# projeson1.net
KiCad netlist of a schematic drawn in EAGLE
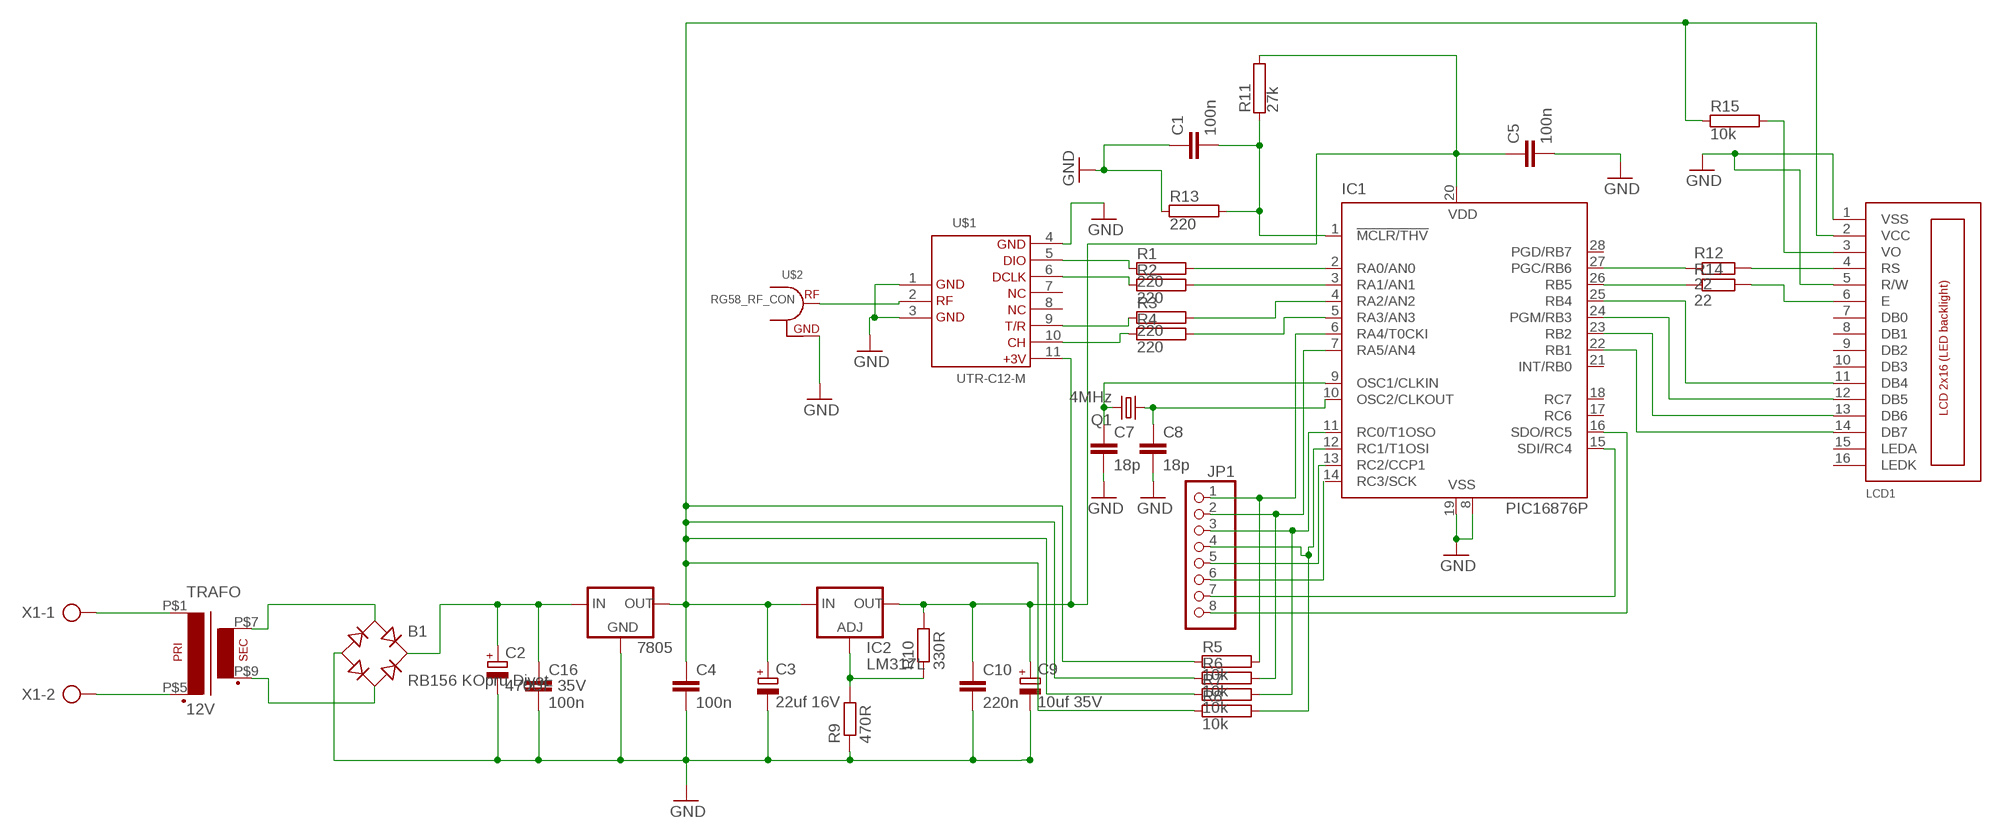
[diagram p0: schematic, sheet 1]

(export (version "E")
  (design (tool "Eeschema 10.0.6"))
  (components
    (comp (ref "7805")
      (value "78XXS")
      (footprint "eagle-import:78XXS")
      (libsource (lib "eagle-import") (part "78XXS"))
    )
    (comp (ref "B1")
      (value "RB156 KOpru Diyot")
      (footprint "eagle-import:RB1A")
      (libsource (lib "eagle-import") (part "RB1A"))
    )
    (comp (ref "C1")
      (value "100n")
      (footprint "eagle-import:C025-030X050")
      (libsource (lib "eagle-import") (part "C-EU025-030X050"))
    )
    (comp (ref "C2")
      (value "470UF 35V")
      (footprint "eagle-import:E3,5-10")
      (libsource (lib "eagle-import") (part "CPOL-EUE3.5-10"))
    )
    (comp (ref "C3")
      (value "22uf 16V")
      (footprint "eagle-import:E2,5-7")
      (libsource (lib "eagle-import") (part "CPOL-EUE2.5-7"))
    )
    (comp (ref "C4")
      (value "100n")
      (footprint "eagle-import:C050-025X075")
      (libsource (lib "eagle-import") (part "C-EU050-025X075"))
    )
    (comp (ref "C5")
      (value "100n")
      (footprint "eagle-import:C025-025X050")
      (libsource (lib "eagle-import") (part "C-EU025-025X050"))
    )
    (comp (ref "C7")
      (value "18p")
      (footprint "eagle-import:C025-025X050")
      (libsource (lib "eagle-import") (part "C-EU025-025X050"))
    )
    (comp (ref "C8")
      (value "18p")
      (footprint "eagle-import:C025-025X050")
      (libsource (lib "eagle-import") (part "C-EU025-025X050"))
    )
    (comp (ref "C9")
      (value "10uf 35V")
      (footprint "eagle-import:E2,5-7")
      (libsource (lib "eagle-import") (part "CPOL-EUE2.5-7"))
    )
    (comp (ref "C10")
      (value "220n")
      (footprint "eagle-import:C050-025X075")
      (libsource (lib "eagle-import") (part "C-EU050-025X075"))
    )
    (comp (ref "C16")
      (value "100n")
      (footprint "eagle-import:C050-025X075")
      (libsource (lib "eagle-import") (part "C-EU050-025X075"))
    )
    (comp (ref "IC1")
      (value "PIC16876P")
      (footprint "eagle-import:DIL28-3")
      (libsource (lib "eagle-import") (part "PIC16876P"))
    )
    (comp (ref "IC2")
      (value "LM317L")
      (footprint "eagle-import:317L")
      (libsource (lib "eagle-import") (part "LM317L"))
    )
    (comp (ref "JP1")
      (value "PINHD-1X8")
      (footprint "eagle-import:1X08")
      (libsource (lib "eagle-import") (part "PINHD-1X8"))
    )
    (comp (ref "LCD1")
      (value "LCD_2X16_SIL")
      (footprint "eagle-import:HY-1602F")
      (libsource (lib "eagle-import") (part "LCD_2X16_SIL"))
    )
    (comp (ref "Q1")
      (value "4MHz")
      (footprint "eagle-import:HC49_S")
      (libsource (lib "eagle-import") (part "CRYTALHC49S"))
    )
    (comp (ref "R1")
      (value "220")
      (footprint "eagle-import:AC04")
      (libsource (lib "eagle-import") (part "RAC04"))
    )
    (comp (ref "R2")
      (value "220")
      (footprint "eagle-import:AC04")
      (libsource (lib "eagle-import") (part "RAC04"))
    )
    (comp (ref "R3")
      (value "220")
      (footprint "eagle-import:AC04")
      (libsource (lib "eagle-import") (part "RAC04"))
    )
    (comp (ref "R4")
      (value "220")
      (footprint "eagle-import:AC04")
      (libsource (lib "eagle-import") (part "RAC04"))
    )
    (comp (ref "R5")
      (value "10k")
      (footprint "eagle-import:AC04")
      (libsource (lib "eagle-import") (part "RAC04"))
    )
    (comp (ref "R6")
      (value "10k")
      (footprint "eagle-import:AC04")
      (libsource (lib "eagle-import") (part "RAC04"))
    )
    (comp (ref "R7")
      (value "10k")
      (footprint "eagle-import:AC04")
      (libsource (lib "eagle-import") (part "RAC04"))
    )
    (comp (ref "R8")
      (value "10k")
      (footprint "eagle-import:AC04")
      (libsource (lib "eagle-import") (part "RAC04"))
    )
    (comp (ref "R9")
      (value "470R")
      (footprint "eagle-import:0207_10")
      (libsource (lib "eagle-import") (part "R-EU_0207/10"))
    )
    (comp (ref "R10")
      (value "330R")
      (footprint "eagle-import:0207_10")
      (libsource (lib "eagle-import") (part "R-EU_0207/10"))
    )
    (comp (ref "R11")
      (value "27k")
      (footprint "eagle-import:AC04")
      (libsource (lib "eagle-import") (part "RAC04"))
    )
    (comp (ref "R12")
      (value "22")
      (footprint "eagle-import:0204_5")
      (libsource (lib "eagle-import") (part "R-EU_0204/5"))
    )
    (comp (ref "R13")
      (value "220")
      (footprint "eagle-import:AC04")
      (libsource (lib "eagle-import") (part "RAC04"))
    )
    (comp (ref "R14")
      (value "22")
      (footprint "eagle-import:0204_5")
      (libsource (lib "eagle-import") (part "R-EU_0204/5"))
    )
    (comp (ref "R15")
      (value "10k")
      (footprint "eagle-import:AC04")
      (libsource (lib "eagle-import") (part "RAC04"))
    )
    (comp (ref "TRAFO")
      (value "12V")
      (footprint "eagle-import:E3031TRF")
      (libsource (lib "eagle-import") (part "TRAFO"))
    )
    (comp (ref "U$1")
      (value "UTR-C12-M")
      (footprint "eagle-import:UTR-C12-M")
      (libsource (lib "eagle-import") (part "UTR-C12-M"))
    )
    (comp (ref "U$2")
      (value "RG58_RF_CON")
      (footprint "eagle-import:RG58_RF_CON")
      (libsource (lib "eagle-import") (part "RG58_RF_CON"))
    )
    (comp (ref "X1")
      (value "AK300/3")
      (footprint "eagle-import:AK300_3")
      (libsource (lib "eagle-import") (part "AK300/3"))
    )
  )
  (nets
    (net (code "1") (name "GND") (class "Default")
      (node (ref "7805") (pin "GND") (pinfunction "GND_GND") (pintype "input"))
      (node (ref "B1") (pin "-") (pinfunction "-_-") (pintype "passive"))
      (node (ref "C1") (pin "1") (pinfunction "1_1") (pintype "passive"))
      (node (ref "C10") (pin "2") (pinfunction "2_2") (pintype "passive"))
      (node (ref "C16") (pin "2") (pinfunction "2_2") (pintype "passive"))
      (node (ref "C2") (pin "-") (pinfunction "-_-") (pintype "passive"))
      (node (ref "C3") (pin "-") (pinfunction "-_-") (pintype "passive"))
      (node (ref "C4") (pin "2") (pinfunction "2_2") (pintype "passive"))
      (node (ref "C5") (pin "2") (pinfunction "2_2") (pintype "passive"))
      (node (ref "C7") (pin "2") (pinfunction "2_2") (pintype "passive"))
      (node (ref "C8") (pin "2") (pinfunction "2_2") (pintype "passive"))
      (node (ref "C9") (pin "-") (pinfunction "-_-") (pintype "passive"))
      (node (ref "IC1") (pin "19") (pinfunction "VSS_19") (pintype "power_in"))
      (node (ref "IC1") (pin "8") (pinfunction "VSS_8") (pintype "power_in"))
      (node (ref "LCD1") (pin "1") (pinfunction "VSS_1") (pintype "power_in"))
      (node (ref "LCD1") (pin "5") (pinfunction "R/W_5") (pintype "input"))
      (node (ref "R13") (pin "1") (pinfunction "1_1") (pintype "passive"))
      (node (ref "R9") (pin "1") (pinfunction "1_1") (pintype "passive"))
      (node (ref "U$1") (pin "1") (pinfunction "1_1") (pintype "bidirectional"))
      (node (ref "U$1") (pin "3") (pinfunction "3_3") (pintype "bidirectional"))
      (node (ref "U$1") (pin "4") (pinfunction "4_4") (pintype "bidirectional"))
      (node (ref "U$2") (pin "GND") (pinfunction "GND_GND") (pintype "bidirectional"))
    )
    (net (code "2") (name "Net-(7805-PadIN)") (class "Default")
      (node (ref "7805") (pin "IN") (pinfunction "IN_IN") (pintype "input"))
      (node (ref "B1") (pin "+") (pinfunction "+_+") (pintype "passive"))
      (node (ref "C16") (pin "1") (pinfunction "1_1") (pintype "passive"))
      (node (ref "C2") (pin "+") (pinfunction "+_+") (pintype "passive"))
    )
    (net (code "3") (name "Net-(IC1-OSC1{slash}CLKIN)") (class "Default")
      (node (ref "C7") (pin "1") (pinfunction "1_1") (pintype "passive"))
      (node (ref "IC1") (pin "9") (pinfunction "OSC1/CLKIN_9") (pintype "input"))
      (node (ref "Q1") (pin "2") (pinfunction "2_2") (pintype "passive"))
    )
    (net (code "4") (name "Net-(IC1-OSC2{slash}CLKOUT)") (class "Default")
      (node (ref "C8") (pin "1") (pinfunction "1_1") (pintype "passive"))
      (node (ref "IC1") (pin "10") (pinfunction "OSC2/CLKOUT_10") (pintype "output"))
      (node (ref "Q1") (pin "1") (pinfunction "1_1") (pintype "passive"))
    )
    (net (code "5") (name "Net-(IC1-PGC{slash}RB6)") (class "Default")
      (node (ref "IC1") (pin "27") (pinfunction "PGC/RB6_27") (pintype "bidirectional"))
      (node (ref "R12") (pin "1") (pinfunction "1_1") (pintype "passive"))
    )
    (net (code "6") (name "Net-(IC1-PGM{slash}RB3)") (class "Default")
      (node (ref "IC1") (pin "24") (pinfunction "PGM/RB3_24") (pintype "bidirectional"))
      (node (ref "LCD1") (pin "12") (pinfunction "DB5_12") (pintype "bidirectional"))
    )
    (net (code "7") (name "Net-(IC1-RA0{slash}AN0)") (class "Default")
      (node (ref "IC1") (pin "2") (pinfunction "RA0/AN0_2") (pintype "bidirectional"))
      (node (ref "R1") (pin "2") (pinfunction "2_2") (pintype "passive"))
    )
    (net (code "8") (name "Net-(IC1-RA1{slash}AN1)") (class "Default")
      (node (ref "IC1") (pin "3") (pinfunction "RA1/AN1_3") (pintype "bidirectional"))
      (node (ref "R2") (pin "2") (pinfunction "2_2") (pintype "passive"))
    )
    (net (code "9") (name "Net-(IC1-RA2{slash}AN2)") (class "Default")
      (node (ref "IC1") (pin "4") (pinfunction "RA2/AN2_4") (pintype "bidirectional"))
      (node (ref "R3") (pin "2") (pinfunction "2_2") (pintype "passive"))
    )
    (net (code "10") (name "Net-(IC1-RA3{slash}AN3)") (class "Default")
      (node (ref "IC1") (pin "5") (pinfunction "RA3/AN3_5") (pintype "bidirectional"))
      (node (ref "R4") (pin "2") (pinfunction "2_2") (pintype "passive"))
    )
    (net (code "11") (name "Net-(IC1-RA4{slash}T0CKI)") (class "Default")
      (node (ref "IC1") (pin "6") (pinfunction "RA4/T0CKI_6") (pintype "bidirectional"))
      (node (ref "JP1") (pin "1") (pinfunction "1_1") (pintype "passive"))
      (node (ref "R5") (pin "2") (pinfunction "2_2") (pintype "passive"))
    )
    (net (code "12") (name "Net-(IC1-RA5{slash}AN4)") (class "Default")
      (node (ref "IC1") (pin "7") (pinfunction "RA5/AN4_7") (pintype "bidirectional"))
      (node (ref "JP1") (pin "2") (pinfunction "2_2") (pintype "passive"))
      (node (ref "R6") (pin "2") (pinfunction "2_2") (pintype "passive"))
    )
    (net (code "13") (name "Net-(IC1-RB1)") (class "Default")
      (node (ref "IC1") (pin "22") (pinfunction "RB1_22") (pintype "bidirectional"))
      (node (ref "LCD1") (pin "14") (pinfunction "DB7_14") (pintype "bidirectional"))
    )
    (net (code "14") (name "Net-(IC1-RB2)") (class "Default")
      (node (ref "IC1") (pin "23") (pinfunction "RB2_23") (pintype "bidirectional"))
      (node (ref "LCD1") (pin "13") (pinfunction "DB6_13") (pintype "bidirectional"))
    )
    (net (code "15") (name "Net-(IC1-RB4)") (class "Default")
      (node (ref "IC1") (pin "25") (pinfunction "RB4_25") (pintype "bidirectional"))
      (node (ref "LCD1") (pin "11") (pinfunction "DB4_11") (pintype "bidirectional"))
    )
    (net (code "16") (name "Net-(IC1-RB5)") (class "Default")
      (node (ref "IC1") (pin "26") (pinfunction "RB5_26") (pintype "bidirectional"))
      (node (ref "R14") (pin "1") (pinfunction "1_1") (pintype "passive"))
    )
    (net (code "17") (name "Net-(IC1-RC0{slash}T1OSO)") (class "Default")
      (node (ref "IC1") (pin "11") (pinfunction "RC0/T1OSO_11") (pintype "bidirectional"))
      (node (ref "JP1") (pin "3") (pinfunction "3_3") (pintype "passive"))
      (node (ref "R7") (pin "2") (pinfunction "2_2") (pintype "passive"))
    )
    (net (code "18") (name "Net-(IC1-RC1{slash}T1OSI)") (class "Default")
      (node (ref "IC1") (pin "12") (pinfunction "RC1/T1OSI_12") (pintype "bidirectional"))
      (node (ref "JP1") (pin "4") (pinfunction "4_4") (pintype "passive"))
      (node (ref "R8") (pin "2") (pinfunction "2_2") (pintype "passive"))
    )
    (net (code "19") (name "Net-(IC1-RC2{slash}CCP1)") (class "Default")
      (node (ref "IC1") (pin "13") (pinfunction "RC2/CCP1_13") (pintype "bidirectional"))
      (node (ref "JP1") (pin "5") (pinfunction "5_5") (pintype "passive"))
    )
    (net (code "20") (name "Net-(IC1-SDI{slash}RC4)") (class "Default")
      (node (ref "IC1") (pin "15") (pinfunction "SDI/RC4_15") (pintype "bidirectional"))
      (node (ref "JP1") (pin "7") (pinfunction "7_7") (pintype "passive"))
    )
    (net (code "21") (name "Net-(IC1-SDO{slash}RC5)") (class "Default")
      (node (ref "IC1") (pin "16") (pinfunction "SDO/RC5_16") (pintype "bidirectional"))
      (node (ref "JP1") (pin "8") (pinfunction "8_8") (pintype "passive"))
    )
    (net (code "22") (name "Net-(IC1-VDD)") (class "Default")
      (node (ref "C10") (pin "1") (pinfunction "1_1") (pintype "passive"))
      (node (ref "C5") (pin "1") (pinfunction "1_1") (pintype "passive"))
      (node (ref "C9") (pin "+") (pinfunction "+_+") (pintype "passive"))
      (node (ref "IC1") (pin "20") (pinfunction "VDD_20") (pintype "power_in"))
      (node (ref "IC2") (pin "2") (pinfunction "OUT_2") (pintype "passive"))
      (node (ref "R10") (pin "2") (pinfunction "2_2") (pintype "passive"))
      (node (ref "R11") (pin "2") (pinfunction "2_2") (pintype "passive"))
      (node (ref "U$1") (pin "11") (pinfunction "11_11") (pintype "bidirectional"))
    )
    (net (code "23") (name "Net-(IC1-~{MCLR{slash}THV})") (class "Default")
      (node (ref "C1") (pin "2") (pinfunction "2_2") (pintype "passive"))
      (node (ref "IC1") (pin "1") (pinfunction "~{MCLR/THV}_1") (pintype "input"))
      (node (ref "R11") (pin "1") (pinfunction "1_1") (pintype "passive"))
      (node (ref "R13") (pin "2") (pinfunction "2_2") (pintype "passive"))
    )
    (net (code "24") (name "Net-(IC2-ADJ)") (class "Default")
      (node (ref "IC2") (pin "1") (pinfunction "ADJ_1") (pintype "input"))
      (node (ref "R10") (pin "1") (pinfunction "1_1") (pintype "passive"))
      (node (ref "R9") (pin "2") (pinfunction "2_2") (pintype "passive"))
    )
    (net (code "25") (name "Net-(IC2-IN)") (class "Default")
      (node (ref "7805") (pin "OUT") (pinfunction "OUT_OUT") (pintype "passive"))
      (node (ref "C3") (pin "+") (pinfunction "+_+") (pintype "passive"))
      (node (ref "C4") (pin "1") (pinfunction "1_1") (pintype "passive"))
      (node (ref "IC2") (pin "3") (pinfunction "IN_3") (pintype "input"))
      (node (ref "LCD1") (pin "2") (pinfunction "VCC_2") (pintype "power_in"))
      (node (ref "R15") (pin "1") (pinfunction "1_1") (pintype "passive"))
      (node (ref "R5") (pin "1") (pinfunction "1_1") (pintype "passive"))
      (node (ref "R6") (pin "1") (pinfunction "1_1") (pintype "passive"))
      (node (ref "R7") (pin "1") (pinfunction "1_1") (pintype "passive"))
      (node (ref "R8") (pin "1") (pinfunction "1_1") (pintype "passive"))
    )
    (net (code "26") (name "Net-(LCD1-E)") (class "Default")
      (node (ref "LCD1") (pin "6") (pinfunction "E_6") (pintype "input"))
      (node (ref "R14") (pin "2") (pinfunction "2_2") (pintype "passive"))
    )
    (net (code "27") (name "Net-(LCD1-RS)") (class "Default")
      (node (ref "LCD1") (pin "4") (pinfunction "RS_4") (pintype "input"))
      (node (ref "R12") (pin "2") (pinfunction "2_2") (pintype "passive"))
    )
    (net (code "28") (name "Net-(LCD1-VO)") (class "Default")
      (node (ref "LCD1") (pin "3") (pinfunction "VO_3") (pintype "input"))
      (node (ref "R15") (pin "2") (pinfunction "2_2") (pintype "passive"))
    )
    (net (code "29") (name "Net-(R1-Pad1)") (class "Default")
      (node (ref "R1") (pin "1") (pinfunction "1_1") (pintype "passive"))
      (node (ref "U$1") (pin "5") (pinfunction "5_5") (pintype "bidirectional"))
    )
    (net (code "30") (name "Net-(R2-Pad1)") (class "Default")
      (node (ref "R2") (pin "1") (pinfunction "1_1") (pintype "passive"))
      (node (ref "U$1") (pin "6") (pinfunction "6_6") (pintype "bidirectional"))
    )
    (net (code "31") (name "Net-(R3-Pad1)") (class "Default")
      (node (ref "R3") (pin "1") (pinfunction "1_1") (pintype "passive"))
      (node (ref "U$1") (pin "9") (pinfunction "9_9") (pintype "bidirectional"))
    )
    (net (code "32") (name "Net-(R4-Pad1)") (class "Default")
      (node (ref "R4") (pin "1") (pinfunction "1_1") (pintype "passive"))
      (node (ref "U$1") (pin "10") (pinfunction "10_10") (pintype "bidirectional"))
    )
    (net (code "33") (name "Net-(TRAFO-1)") (class "Default")
      (node (ref "TRAFO") (pin "P$1") (pinfunction "1_P$1") (pintype "passive"))
      (node (ref "X1") (pin "1") (pinfunction "KL_1") (pintype "passive"))
    )
    (net (code "34") (name "Net-(TRAFO-5)") (class "Default")
      (node (ref "TRAFO") (pin "P$5") (pinfunction "5_P$5") (pintype "passive"))
      (node (ref "X1") (pin "2") (pinfunction "KL_2") (pintype "passive"))
    )
    (net (code "35") (name "Net-(TRAFO-7)") (class "Default")
      (node (ref "B1") (pin "AC1") (pinfunction "AC1_AC1") (pintype "passive"))
      (node (ref "TRAFO") (pin "P$7") (pinfunction "7_P$7") (pintype "passive"))
    )
    (net (code "36") (name "Net-(TRAFO-9)") (class "Default")
      (node (ref "B1") (pin "AC2") (pinfunction "AC2_AC2") (pintype "passive"))
      (node (ref "TRAFO") (pin "P$9") (pinfunction "9_P$9") (pintype "passive"))
    )
    (net (code "37") (name "Net-(U$1-Pad2)") (class "Default")
      (node (ref "U$1") (pin "2") (pinfunction "2_2") (pintype "bidirectional"))
      (node (ref "U$2") (pin "RF") (pinfunction "RF_RF") (pintype "bidirectional"))
    )
    (net (code "38") (name "unconnected-(IC1-INT{slash}RB0-Pad21)") (class "Default")
      (node (ref "IC1") (pin "21") (pinfunction "INT/RB0_21") (pintype "bidirectional"))
    )
    (net (code "39") (name "unconnected-(IC1-PGD{slash}RB7-Pad28)") (class "Default")
      (node (ref "IC1") (pin "28") (pinfunction "PGD/RB7_28") (pintype "bidirectional"))
    )
    (net (code "40") (name "unconnected-(IC1-RC3{slash}SCK-Pad14)") (class "Default")
      (node (ref "IC1") (pin "14") (pinfunction "RC3/SCK_14") (pintype "bidirectional"))
    )
    (net (code "41") (name "unconnected-(IC1-RC6-Pad17)") (class "Default")
      (node (ref "IC1") (pin "17") (pinfunction "RC6_17") (pintype "bidirectional"))
    )
    (net (code "42") (name "unconnected-(IC1-RC7-Pad18)") (class "Default")
      (node (ref "IC1") (pin "18") (pinfunction "RC7_18") (pintype "bidirectional"))
    )
    (net (code "43") (name "unconnected-(JP1-Pad6)") (class "Default")
      (node (ref "JP1") (pin "6") (pinfunction "6_6") (pintype "passive"))
    )
    (net (code "44") (name "unconnected-(LCD1-DB0-Pad7)") (class "Default")
      (node (ref "LCD1") (pin "7") (pinfunction "DB0_7") (pintype "bidirectional"))
    )
    (net (code "45") (name "unconnected-(LCD1-DB1-Pad8)") (class "Default")
      (node (ref "LCD1") (pin "8") (pinfunction "DB1_8") (pintype "bidirectional"))
    )
    (net (code "46") (name "unconnected-(LCD1-DB2-Pad9)") (class "Default")
      (node (ref "LCD1") (pin "9") (pinfunction "DB2_9") (pintype "bidirectional"))
    )
    (net (code "47") (name "unconnected-(LCD1-DB3-Pad10)") (class "Default")
      (node (ref "LCD1") (pin "10") (pinfunction "DB3_10") (pintype "bidirectional"))
    )
    (net (code "48") (name "unconnected-(LCD1-LEDA-Pad15)") (class "Default")
      (node (ref "LCD1") (pin "15") (pinfunction "LEDA_15") (pintype "passive"))
    )
    (net (code "49") (name "unconnected-(LCD1-LEDK-Pad16)") (class "Default")
      (node (ref "LCD1") (pin "16") (pinfunction "LEDK_16") (pintype "passive"))
    )
    (net (code "50") (name "unconnected-(U$1-Pad7)") (class "Default")
      (node (ref "U$1") (pin "7") (pinfunction "7_7") (pintype "bidirectional"))
    )
    (net (code "51") (name "unconnected-(U$1-Pad8)") (class "Default")
      (node (ref "U$1") (pin "8") (pinfunction "8_8") (pintype "bidirectional"))
    )
  )
)
